# BeeTermostat.net
KiCad netlist of a schematic drawn in EAGLE
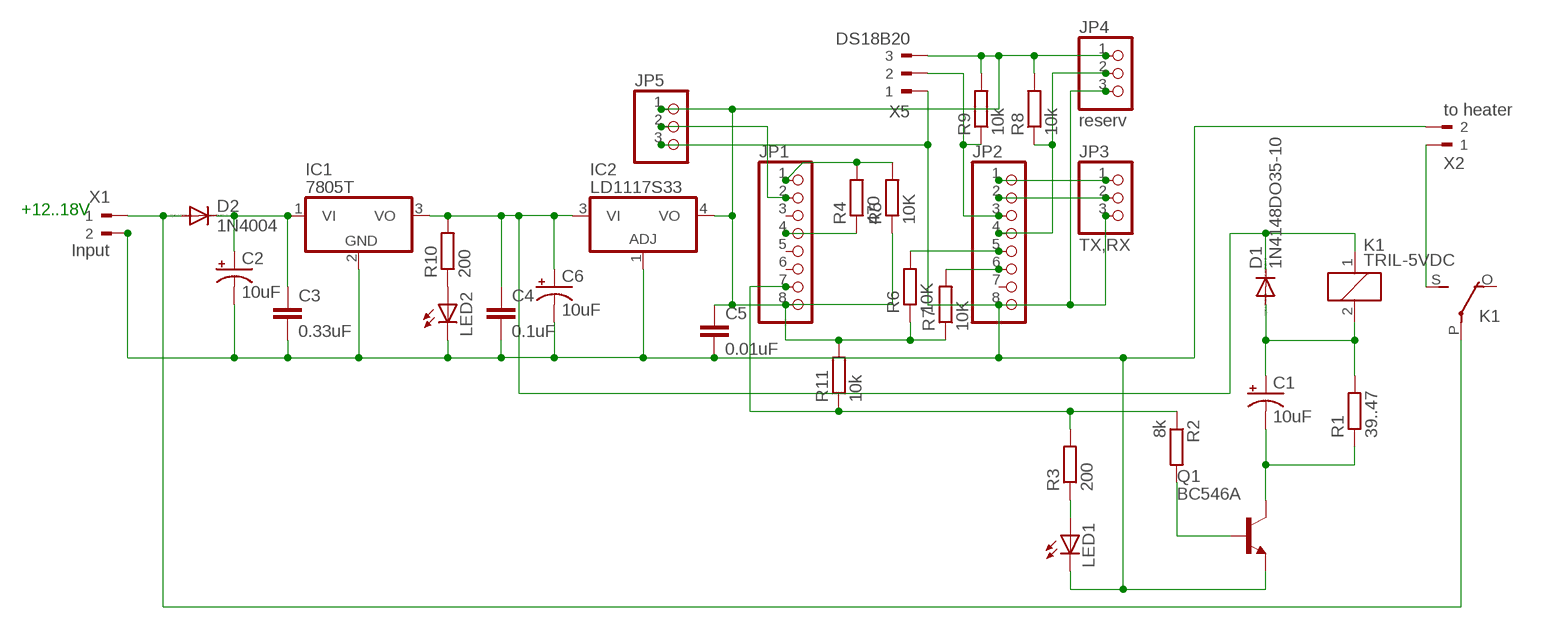
[diagram p0: schematic, sheet 1]

(export (version "E")
  (design (tool "Eeschema 10.0.6"))
  (components
    (comp (ref "C1")
      (value "10uF")
      (footprint "eagle-import:E2,5-5")
      (libsource (lib "eagle-import") (part "CPOL-USE2.5-5"))
    )
    (comp (ref "C2")
      (value "10uF")
      (footprint "eagle-import:E2,5-5")
      (libsource (lib "eagle-import") (part "CPOL-USE2.5-5"))
    )
    (comp (ref "C3")
      (value "0.33uF")
      (footprint "eagle-import:C050-025X075")
      (libsource (lib "eagle-import") (part "C-EU050-025X075"))
    )
    (comp (ref "C4")
      (value "0.1uF")
      (footprint "eagle-import:C050-025X075")
      (libsource (lib "eagle-import") (part "C-EU050-025X075"))
    )
    (comp (ref "C5")
      (value "0.01uF")
      (footprint "eagle-import:C0805")
      (libsource (lib "eagle-import") (part "C-EUC0805"))
    )
    (comp (ref "C6")
      (value "10uF")
      (footprint "eagle-import:E5-8,5")
      (libsource (lib "eagle-import") (part "CPOL-USE5-8.5"))
    )
    (comp (ref "D1")
      (value "1N4148DO35-10")
      (footprint "eagle-import:DO35-10")
      (libsource (lib "eagle-import") (part "1N4148DO35-10"))
    )
    (comp (ref "D2")
      (value "1N4004")
      (footprint "eagle-import:DO41-10")
      (libsource (lib "eagle-import") (part "1N4004"))
    )
    (comp (ref "IC1")
      (value "7805T")
      (footprint "eagle-import:TO220H")
      (libsource (lib "eagle-import") (part "78T05"))
    )
    (comp (ref "IC2")
      (value "LD1117S33")
      (footprint "eagle-import:SOT223")
      (libsource (lib "eagle-import") (part "317EMP"))
    )
    (comp (ref "JP1")
      (value "PINHD-1X8")
      (footprint "eagle-import:1X08")
      (libsource (lib "eagle-import") (part "PINHD-1X8"))
    )
    (comp (ref "JP2")
      (value "PINHD-1X8")
      (footprint "eagle-import:1X08")
      (libsource (lib "eagle-import") (part "PINHD-1X8"))
    )
    (comp (ref "JP3")
      (value "TX,RX")
      (footprint "eagle-import:1X03")
      (libsource (lib "eagle-import") (part "PINHD-1X3"))
    )
    (comp (ref "JP4")
      (value "reserv")
      (footprint "eagle-import:1X03")
      (libsource (lib "eagle-import") (part "PINHD-1X3"))
    )
    (comp (ref "JP5")
      (value "PINHD-1X3")
      (footprint "eagle-import:1X03")
      (libsource (lib "eagle-import") (part "PINHD-1X3"))
    )
    (comp (ref "K1")
      (value "TRIL-5VDC")
      (footprint "eagle-import:E3206S")
      (libsource (lib "eagle-import") (part "E3206S"))
    )
    (comp (ref "LED1")
      (value "LED5MM")
      (footprint "eagle-import:LED5MM")
      (libsource (lib "eagle-import") (part "LED5MM"))
    )
    (comp (ref "LED2")
      (value "LED5MM")
      (footprint "eagle-import:LED5MM")
      (libsource (lib "eagle-import") (part "LED5MM"))
    )
    (comp (ref "Q1")
      (value "BC546A")
      (footprint "eagle-import:TO92-EBC")
      (libsource (lib "eagle-import") (part "BC546A"))
    )
    (comp (ref "R1")
      (value "39..47")
      (footprint "eagle-import:0309_12")
      (libsource (lib "eagle-import") (part "R-EU_0309/12"))
    )
    (comp (ref "R2")
      (value "8k")
      (footprint "eagle-import:0309_12")
      (libsource (lib "eagle-import") (part "R-EU_0309/12"))
    )
    (comp (ref "R3")
      (value "200")
      (footprint "eagle-import:0309_12")
      (libsource (lib "eagle-import") (part "R-EU_0309/12"))
    )
    (comp (ref "R4")
      (value "470")
      (footprint "eagle-import:M0805")
      (libsource (lib "eagle-import") (part "R-EU_M0805"))
    )
    (comp (ref "R5")
      (value "10K")
      (footprint "eagle-import:M0805")
      (libsource (lib "eagle-import") (part "R-EU_M0805"))
    )
    (comp (ref "R6")
      (value "10K")
      (footprint "eagle-import:M0805")
      (libsource (lib "eagle-import") (part "R-EU_M0805"))
    )
    (comp (ref "R7")
      (value "10K")
      (footprint "eagle-import:M0805")
      (libsource (lib "eagle-import") (part "R-EU_M0805"))
    )
    (comp (ref "R8")
      (value "10k")
      (footprint "eagle-import:M0805")
      (libsource (lib "eagle-import") (part "R-EU_M0805"))
    )
    (comp (ref "R9")
      (value "10k")
      (footprint "eagle-import:M0805")
      (libsource (lib "eagle-import") (part "R-EU_M0805"))
    )
    (comp (ref "R10")
      (value "200")
      (footprint "eagle-import:0207_10")
      (libsource (lib "eagle-import") (part "R-EU_0207/10"))
    )
    (comp (ref "R11")
      (value "10k")
      (footprint "eagle-import:M0805")
      (libsource (lib "eagle-import") (part "R-EU_M0805"))
    )
    (comp (ref "X1")
      (value "Input")
      (footprint "eagle-import:90-2")
      (libsource (lib "eagle-import") (part "90-2"))
    )
    (comp (ref "X2")
      (value "to heater")
      (footprint "eagle-import:90-2")
      (libsource (lib "eagle-import") (part "90-2"))
    )
    (comp (ref "X5")
      (value "DS18B20")
      (footprint "eagle-import:90-3")
      (libsource (lib "eagle-import") (part "90-3"))
    )
  )
  (nets
    (net (code "1") (name "Net-(C1-Pad+)") (class "Default")
      (node (ref "C1") (pin "+") (pinfunction "+_+") (pintype "passive"))
      (node (ref "D1") (pin "A") (pinfunction "A_A") (pintype "passive"))
      (node (ref "K1") (pin "2") (pinfunction "2_2") (pintype "passive"))
      (node (ref "R1") (pin "2") (pinfunction "2_2") (pintype "passive"))
    )
    (net (code "2") (name "Net-(C1-Pad-)") (class "Default")
      (node (ref "C1") (pin "-") (pinfunction "-_-") (pintype "passive"))
      (node (ref "Q1") (pin "C") (pinfunction "C_C") (pintype "passive"))
      (node (ref "R1") (pin "1") (pinfunction "1_1") (pintype "passive"))
    )
    (net (code "3") (name "Net-(D2-PadA)") (class "Default")
      (node (ref "D2") (pin "A") (pinfunction "A_A") (pintype "passive"))
      (node (ref "K1") (pin "P") (pinfunction "P_P") (pintype "passive"))
      (node (ref "X1") (pin "1") (pinfunction "1_1") (pintype "passive"))
    )
    (net (code "4") (name "Net-(IC1-GND)") (class "Default")
      (node (ref "C2") (pin "-") (pinfunction "-_-") (pintype "passive"))
      (node (ref "C3") (pin "2") (pinfunction "2_2") (pintype "passive"))
      (node (ref "C4") (pin "2") (pinfunction "2_2") (pintype "passive"))
      (node (ref "C5") (pin "2") (pinfunction "2_2") (pintype "passive"))
      (node (ref "C6") (pin "-") (pinfunction "-_-") (pintype "passive"))
      (node (ref "IC1") (pin "2") (pinfunction "GND_2") (pintype "passive"))
      (node (ref "IC2") (pin "1") (pinfunction "ADJ_1") (pintype "input"))
      (node (ref "JP2") (pin "8") (pinfunction "8_8") (pintype "passive"))
      (node (ref "JP3") (pin "3") (pinfunction "3_3") (pintype "passive"))
      (node (ref "JP4") (pin "3") (pinfunction "3_3") (pintype "passive"))
      (node (ref "JP5") (pin "3") (pinfunction "3_3") (pintype "passive"))
      (node (ref "LED1") (pin "K") (pinfunction "C_K") (pintype "passive"))
      (node (ref "LED2") (pin "K") (pinfunction "C_K") (pintype "passive"))
      (node (ref "Q1") (pin "E") (pinfunction "E_E") (pintype "passive"))
      (node (ref "X1") (pin "2") (pinfunction "2_2") (pintype "passive"))
      (node (ref "X2") (pin "2") (pinfunction "2_2") (pintype "passive"))
      (node (ref "X5") (pin "1") (pinfunction "1_1") (pintype "passive"))
    )
    (net (code "5") (name "Net-(IC1-VI)") (class "Default")
      (node (ref "C2") (pin "+") (pinfunction "+_+") (pintype "passive"))
      (node (ref "C3") (pin "1") (pinfunction "1_1") (pintype "passive"))
      (node (ref "D2") (pin "C") (pinfunction "C_C") (pintype "passive"))
      (node (ref "IC1") (pin "1") (pinfunction "VI_1") (pintype "input"))
    )
    (net (code "6") (name "Net-(IC1-VO)") (class "Default")
      (node (ref "C4") (pin "1") (pinfunction "1_1") (pintype "passive"))
      (node (ref "C6") (pin "+") (pinfunction "+_+") (pintype "passive"))
      (node (ref "D1") (pin "C") (pinfunction "C_C") (pintype "passive"))
      (node (ref "IC1") (pin "3") (pinfunction "VO_3") (pintype "passive"))
      (node (ref "IC2") (pin "3") (pinfunction "VI_3") (pintype "input"))
      (node (ref "K1") (pin "1") (pinfunction "1_1") (pintype "passive"))
      (node (ref "R10") (pin "2") (pinfunction "2_2") (pintype "passive"))
    )
    (net (code "7") (name "Net-(IC2-VO)") (class "Default")
      (node (ref "C5") (pin "1") (pinfunction "1_1") (pintype "passive"))
      (node (ref "IC2") (pin "4") (pinfunction "VO_4") (pintype "passive"))
      (node (ref "JP1") (pin "8") (pinfunction "8_8") (pintype "passive"))
      (node (ref "JP4") (pin "1") (pinfunction "1_1") (pintype "passive"))
      (node (ref "JP5") (pin "1") (pinfunction "1_1") (pintype "passive"))
      (node (ref "R11") (pin "2") (pinfunction "2_2") (pintype "passive"))
      (node (ref "R5") (pin "1") (pinfunction "1_1") (pintype "passive"))
      (node (ref "R6") (pin "1") (pinfunction "1_1") (pintype "passive"))
      (node (ref "R7") (pin "1") (pinfunction "1_1") (pintype "passive"))
      (node (ref "R8") (pin "2") (pinfunction "2_2") (pintype "passive"))
      (node (ref "R9") (pin "2") (pinfunction "2_2") (pintype "passive"))
      (node (ref "X5") (pin "3") (pinfunction "3_3") (pintype "passive"))
    )
    (net (code "8") (name "Net-(JP1-Pad1)") (class "Default")
      (node (ref "JP1") (pin "1") (pinfunction "1_1") (pintype "passive"))
      (node (ref "R4") (pin "2") (pinfunction "2_2") (pintype "passive"))
      (node (ref "R5") (pin "2") (pinfunction "2_2") (pintype "passive"))
    )
    (net (code "9") (name "Net-(JP1-Pad2)") (class "Default")
      (node (ref "JP1") (pin "2") (pinfunction "2_2") (pintype "passive"))
      (node (ref "JP5") (pin "2") (pinfunction "2_2") (pintype "passive"))
    )
    (net (code "10") (name "Net-(JP1-Pad4)") (class "Default")
      (node (ref "JP1") (pin "4") (pinfunction "4_4") (pintype "passive"))
      (node (ref "R4") (pin "1") (pinfunction "1_1") (pintype "passive"))
    )
    (net (code "11") (name "Net-(JP1-Pad7)") (class "Default")
      (node (ref "JP1") (pin "7") (pinfunction "7_7") (pintype "passive"))
      (node (ref "R11") (pin "1") (pinfunction "1_1") (pintype "passive"))
      (node (ref "R2") (pin "1") (pinfunction "1_1") (pintype "passive"))
      (node (ref "R3") (pin "2") (pinfunction "2_2") (pintype "passive"))
    )
    (net (code "12") (name "Net-(JP2-Pad1)") (class "Default")
      (node (ref "JP2") (pin "1") (pinfunction "1_1") (pintype "passive"))
      (node (ref "JP3") (pin "1") (pinfunction "1_1") (pintype "passive"))
    )
    (net (code "13") (name "Net-(JP2-Pad2)") (class "Default")
      (node (ref "JP2") (pin "2") (pinfunction "2_2") (pintype "passive"))
      (node (ref "JP3") (pin "2") (pinfunction "2_2") (pintype "passive"))
    )
    (net (code "14") (name "Net-(JP2-Pad3)") (class "Default")
      (node (ref "JP2") (pin "3") (pinfunction "3_3") (pintype "passive"))
      (node (ref "R9") (pin "1") (pinfunction "1_1") (pintype "passive"))
      (node (ref "X5") (pin "2") (pinfunction "2_2") (pintype "passive"))
    )
    (net (code "15") (name "Net-(JP2-Pad4)") (class "Default")
      (node (ref "JP2") (pin "4") (pinfunction "4_4") (pintype "passive"))
      (node (ref "JP4") (pin "2") (pinfunction "2_2") (pintype "passive"))
      (node (ref "R8") (pin "1") (pinfunction "1_1") (pintype "passive"))
    )
    (net (code "16") (name "Net-(JP2-Pad5)") (class "Default")
      (node (ref "JP2") (pin "5") (pinfunction "5_5") (pintype "passive"))
      (node (ref "R6") (pin "2") (pinfunction "2_2") (pintype "passive"))
    )
    (net (code "17") (name "Net-(JP2-Pad6)") (class "Default")
      (node (ref "JP2") (pin "6") (pinfunction "6_6") (pintype "passive"))
      (node (ref "R7") (pin "2") (pinfunction "2_2") (pintype "passive"))
    )
    (net (code "18") (name "Net-(K1-PadS)") (class "Default")
      (node (ref "K1") (pin "S") (pinfunction "S_S") (pintype "passive"))
      (node (ref "X2") (pin "1") (pinfunction "1_1") (pintype "passive"))
    )
    (net (code "19") (name "Net-(LED1-PadA)") (class "Default")
      (node (ref "LED1") (pin "A") (pinfunction "A_A") (pintype "passive"))
      (node (ref "R3") (pin "1") (pinfunction "1_1") (pintype "passive"))
    )
    (net (code "20") (name "Net-(LED2-PadA)") (class "Default")
      (node (ref "LED2") (pin "A") (pinfunction "A_A") (pintype "passive"))
      (node (ref "R10") (pin "1") (pinfunction "1_1") (pintype "passive"))
    )
    (net (code "21") (name "Net-(Q1-PadB)") (class "Default")
      (node (ref "Q1") (pin "B") (pinfunction "B_B") (pintype "passive"))
      (node (ref "R2") (pin "2") (pinfunction "2_2") (pintype "passive"))
    )
    (net (code "22") (name "unconnected-(JP1-Pad3)") (class "Default")
      (node (ref "JP1") (pin "3") (pinfunction "3_3") (pintype "passive"))
    )
    (net (code "23") (name "unconnected-(JP1-Pad5)") (class "Default")
      (node (ref "JP1") (pin "5") (pinfunction "5_5") (pintype "passive"))
    )
    (net (code "24") (name "unconnected-(JP1-Pad6)") (class "Default")
      (node (ref "JP1") (pin "6") (pinfunction "6_6") (pintype "passive"))
    )
    (net (code "25") (name "unconnected-(JP2-Pad7)") (class "Default")
      (node (ref "JP2") (pin "7") (pinfunction "7_7") (pintype "passive"))
    )
    (net (code "26") (name "unconnected-(K1-PadO)") (class "Default")
      (node (ref "K1") (pin "O") (pinfunction "O_O") (pintype "passive"))
    )
  )
)
